# NFC.net
KiCad netlist of a schematic drawn in Altium Designer
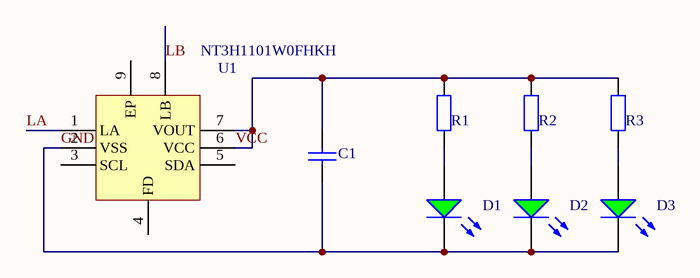
[diagram p0: NFC.SchDoc]

(export (version "E")
  (design (tool "Eeschema 10.0.6"))
  (components
    (comp (ref "C1")
      (value "220nF (224) 10% 50V")
      (footprint "0805_C")
      (description "贴片电容")
      (libsource (lib "Miscellaneous Devices LC") (part "0805 220nF (224) 10% 50V"))
    )
    (comp (ref "D1")
      (value "翠绿 0805")
      (footprint "0805_LED_S1")
      (description "发光二极管")
      (libsource (lib "Miscellaneous Devices LC") (part "0805 翠绿"))
    )
    (comp (ref "D2")
      (value "翠绿 0805")
      (footprint "0805_LED_S1")
      (description "发光二极管")
      (libsource (lib "Miscellaneous Devices LC") (part "0805 翠绿"))
    )
    (comp (ref "D3")
      (value "翠绿 0805")
      (footprint "0805_LED_S1")
      (description "发光二极管")
      (libsource (lib "Miscellaneous Devices LC") (part "0805 翠绿"))
    )
    (comp (ref "R1")
      (value "47Ω (47R0) ±1%")
      (footprint "0805_R")
      (description "贴片电阻")
      (libsource (lib "") (part "0805 47Ω (47R0) 1%_1"))
    )
    (comp (ref "R2")
      (value "47Ω (47R0) ±1%")
      (footprint "0805_R")
      (description "贴片电阻")
      (libsource (lib "Miscellaneous Devices LC") (part "0805 47Ω (47R0) 1%"))
    )
    (comp (ref "R3")
      (value "47Ω (47R0) ±1%")
      (footprint "0805_R")
      (description "贴片电阻")
      (libsource (lib "Miscellaneous Devices LC") (part "0805 47Ω (47R0) 1%"))
    )
    (comp (ref "U1")
      (value "NT3H1101W0FHKH")
      (footprint "XQFN-8_L1.6-W1.6-P0.50-BR")
      (description "NFC芯片")
      (libsource (lib "NFC") (part "NT3H1101W0FHKH"))
    )
  )
  (nets
    (net (code "1") (name "/GND") (class "Default")
      (node (ref "C1") (pin "1") (pinfunction "1_1") (pintype "passive"))
      (node (ref "D1") (pin "K") (pinfunction "K_K") (pintype "passive"))
      (node (ref "D2") (pin "K") (pinfunction "K_K") (pintype "passive"))
      (node (ref "D3") (pin "K") (pinfunction "K_K") (pintype "passive"))
      (node (ref "U1") (pin "2") (pinfunction "VSS_2") (pintype "passive"))
    )
    (net (code "2") (name "/LA") (class "Default")
      (node (ref "U1") (pin "1") (pinfunction "LA_1") (pintype "passive"))
    )
    (net (code "3") (name "/LB") (class "Default")
      (node (ref "U1") (pin "8") (pinfunction "LB_8") (pintype "passive"))
    )
    (net (code "4") (name "/VCC") (class "Default")
      (node (ref "C1") (pin "2") (pinfunction "2_2") (pintype "passive"))
      (node (ref "R1") (pin "2") (pinfunction "2_2") (pintype "passive"))
      (node (ref "R2") (pin "1") (pinfunction "1_1") (pintype "passive"))
      (node (ref "R3") (pin "1") (pinfunction "1_1") (pintype "passive"))
      (node (ref "U1") (pin "6") (pinfunction "VCC_6") (pintype "passive"))
      (node (ref "U1") (pin "7") (pinfunction "VOUT_7") (pintype "passive"))
    )
    (net (code "5") (name "Net-(D1-PadA)") (class "Default")
      (node (ref "D1") (pin "A") (pinfunction "A_A") (pintype "passive"))
      (node (ref "R1") (pin "1") (pinfunction "1_1") (pintype "passive"))
    )
    (net (code "6") (name "Net-(D2-PadA)") (class "Default")
      (node (ref "D2") (pin "A") (pinfunction "A_A") (pintype "passive"))
      (node (ref "R2") (pin "2") (pinfunction "2_2") (pintype "passive"))
    )
    (net (code "7") (name "Net-(D3-PadA)") (class "Default")
      (node (ref "D3") (pin "A") (pinfunction "A_A") (pintype "passive"))
      (node (ref "R3") (pin "2") (pinfunction "2_2") (pintype "passive"))
    )
    (net (code "8") (name "unconnected-(U1-EP-Pad9)") (class "Default")
      (node (ref "U1") (pin "9") (pinfunction "EP_9") (pintype "passive"))
    )
    (net (code "9") (name "unconnected-(U1-FD-Pad4)") (class "Default")
      (node (ref "U1") (pin "4") (pinfunction "FD_4") (pintype "passive"))
    )
    (net (code "10") (name "unconnected-(U1-SCL-Pad3)") (class "Default")
      (node (ref "U1") (pin "3") (pinfunction "SCL_3") (pintype "passive"))
    )
    (net (code "11") (name "unconnected-(U1-SDA-Pad5)") (class "Default")
      (node (ref "U1") (pin "5") (pinfunction "SDA_5") (pintype "passive"))
    )
  )
)
